# UBTB_MIX_old.net
KiCad netlist of a schematic drawn in EAGLE
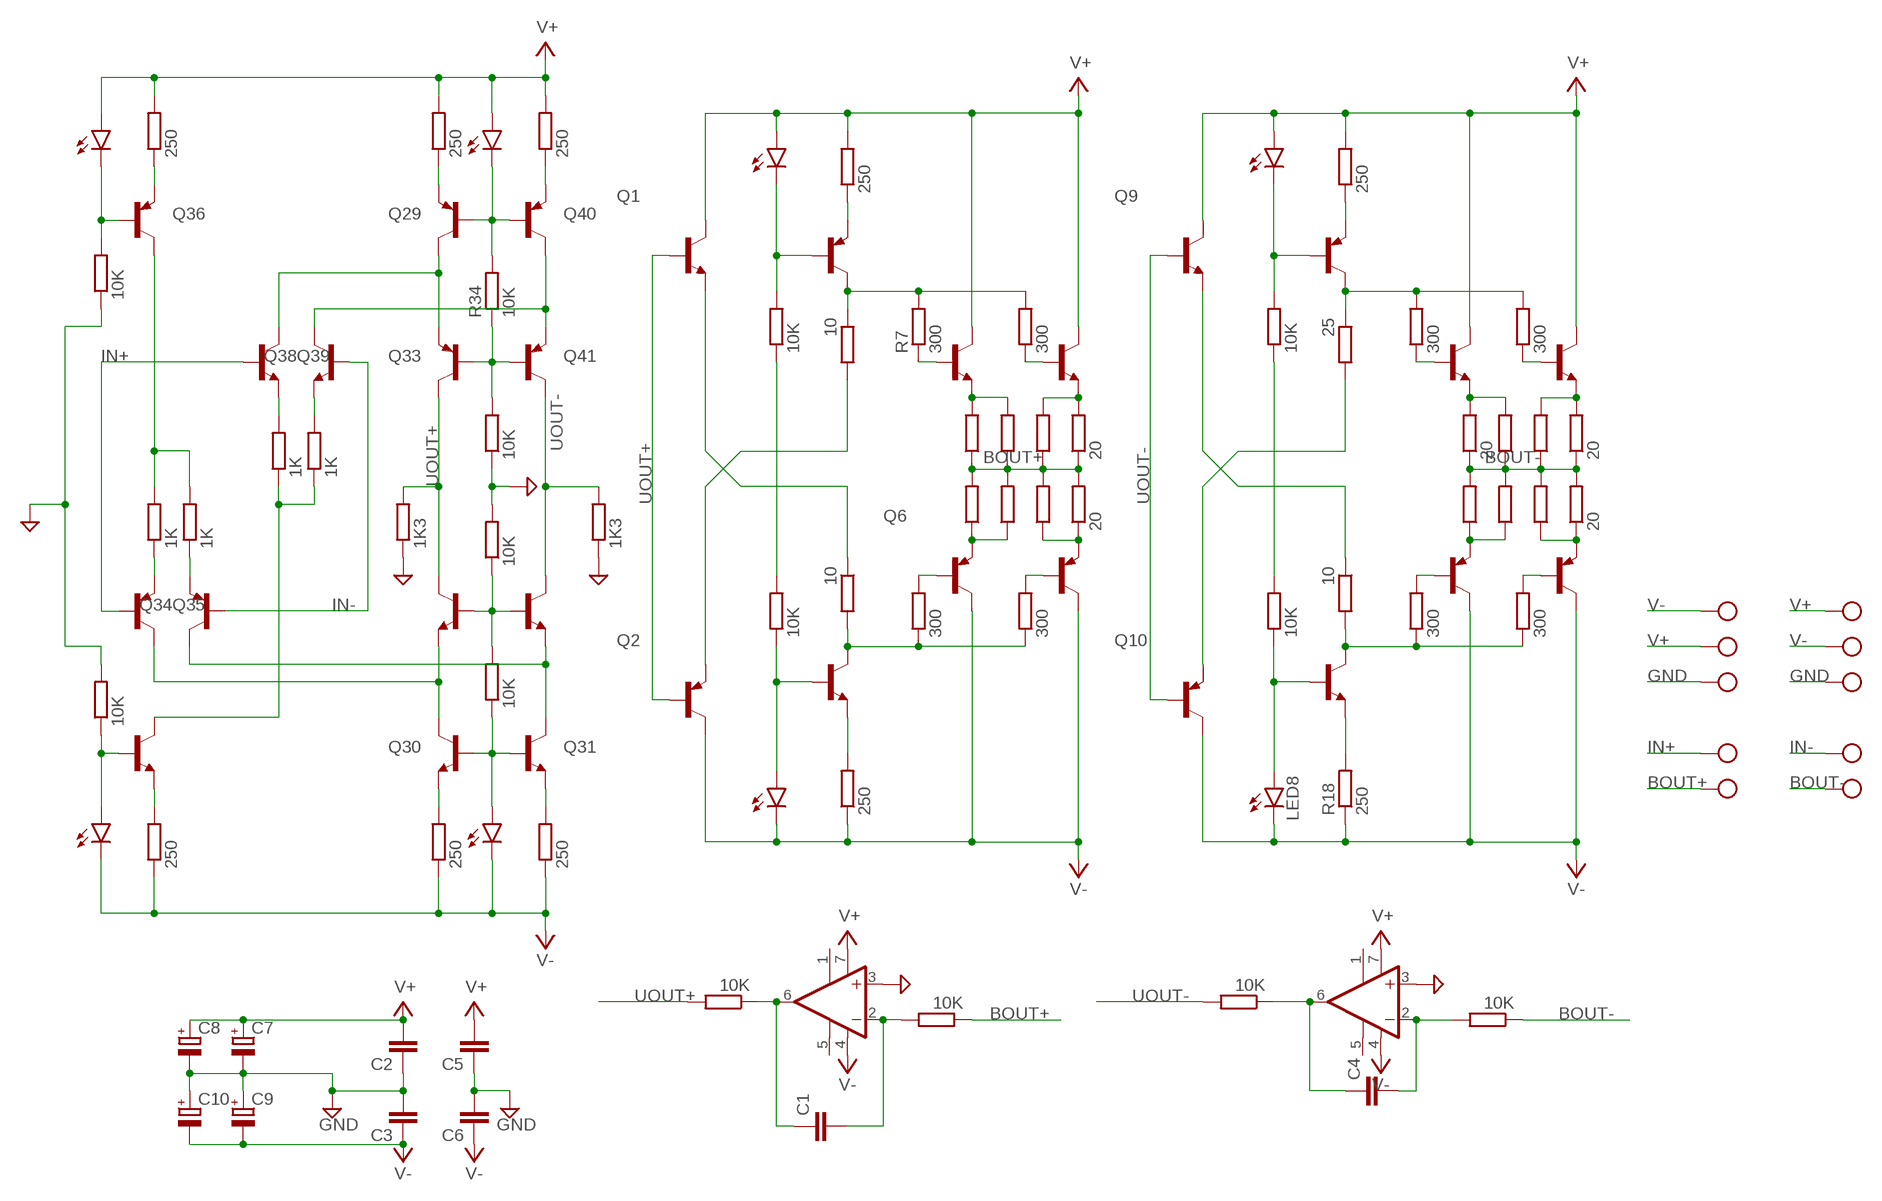
[diagram p0: schematic, sheet 1]

(export (version "E")
  (design (tool "Eeschema 10.0.6"))
  (components
    (comp (ref "C1")
      (value "C-EUC1206")
      (footprint "eagle-import:C1206")
      (libsource (lib "eagle-import") (part "C-EUC1206"))
    )
    (comp (ref "C2")
      (value "C-EUC0805")
      (footprint "eagle-import:C0805")
      (libsource (lib "eagle-import") (part "C-EUC0805"))
    )
    (comp (ref "C3")
      (value "C-EUC0805")
      (footprint "eagle-import:C0805")
      (libsource (lib "eagle-import") (part "C-EUC0805"))
    )
    (comp (ref "C4")
      (value "C-EUC1206")
      (footprint "eagle-import:C1206")
      (libsource (lib "eagle-import") (part "C-EUC1206"))
    )
    (comp (ref "C5")
      (value "C-EUC0805")
      (footprint "eagle-import:C0805")
      (libsource (lib "eagle-import") (part "C-EUC0805"))
    )
    (comp (ref "C6")
      (value "C-EUC0805")
      (footprint "eagle-import:C0805")
      (libsource (lib "eagle-import") (part "C-EUC0805"))
    )
    (comp (ref "C7")
      (value "CPOL-EUF")
      (footprint "eagle-import:PANASONIC_F")
      (libsource (lib "eagle-import") (part "CPOL-EUF"))
    )
    (comp (ref "C8")
      (value "CPOL-EUF")
      (footprint "eagle-import:PANASONIC_F")
      (libsource (lib "eagle-import") (part "CPOL-EUF"))
    )
    (comp (ref "C9")
      (value "CPOL-EUF")
      (footprint "eagle-import:PANASONIC_F")
      (libsource (lib "eagle-import") (part "CPOL-EUF"))
    )
    (comp (ref "C10")
      (value "CPOL-EUF")
      (footprint "eagle-import:PANASONIC_F")
      (libsource (lib "eagle-import") (part "CPOL-EUF"))
    )
    (comp (ref "IC1")
      (value "OPA627U")
      (footprint "eagle-import:SO08")
      (fields (field (name "MF") "TEXAS INSTRUMENTS") (field (name "MPN") "OPA627AU"))
      (libsource (lib "eagle-import") (part "OPA627U"))
    )
    (comp (ref "IC2")
      (value "OPA627U")
      (footprint "eagle-import:SO08")
      (fields (field (name "MF") "TEXAS INSTRUMENTS") (field (name "MPN") "OPA627AU"))
      (libsource (lib "eagle-import") (part "OPA627U"))
    )
    (comp (ref "LED1")
      (value "LEDCHIPLED_1206")
      (footprint "eagle-import:CHIPLED_1206")
      (libsource (lib "eagle-import") (part "LEDCHIPLED_1206"))
    )
    (comp (ref "LED2")
      (value "LEDCHIPLED_1206")
      (footprint "eagle-import:CHIPLED_1206")
      (libsource (lib "eagle-import") (part "LEDCHIPLED_1206"))
    )
    (comp (ref "LED3")
      (value "LEDCHIPLED_1206")
      (footprint "eagle-import:CHIPLED_1206")
      (libsource (lib "eagle-import") (part "LEDCHIPLED_1206"))
    )
    (comp (ref "LED4")
      (value "LEDCHIPLED_1206")
      (footprint "eagle-import:CHIPLED_1206")
      (fields (field (name "SPICEPREFIX") "D"))
      (libsource (lib "eagle-import") (part "LEDCHIPLED_1206"))
    )
    (comp (ref "LED5")
      (value "LEDCHIPLED_1206")
      (footprint "eagle-import:CHIPLED_1206")
      (libsource (lib "eagle-import") (part "LEDCHIPLED_1206"))
    )
    (comp (ref "LED6")
      (value "LEDCHIPLED_1206")
      (footprint "eagle-import:CHIPLED_1206")
      (libsource (lib "eagle-import") (part "LEDCHIPLED_1206"))
    )
    (comp (ref "LED7")
      (value "LEDCHIPLED_1206")
      (footprint "eagle-import:CHIPLED_1206")
      (libsource (lib "eagle-import") (part "LEDCHIPLED_1206"))
    )
    (comp (ref "LED8")
      (value "LEDCHIPLED_1206")
      (footprint "eagle-import:CHIPLED_1206")
      (libsource (lib "eagle-import") (part "LEDCHIPLED_1206"))
    )
    (comp (ref "Q1")
      (value "TRANSISTOR_BC846-NPN-SOT23-BEC")
      (footprint "eagle-import:TRANSISTOR_SOT23-BEC")
      (libsource (lib "eagle-import") (part "TRANSISTOR_-NPN-SOT23-BECBC846"))
    )
    (comp (ref "Q2")
      (value "TRANSISTOR_BC856B-PNP-SOT23-BEC")
      (footprint "eagle-import:TRANSISTOR_SOT23-BEC")
      (libsource (lib "eagle-import") (part "TRANSISTOR_-PNP-SOT23-BECBC856B"))
    )
    (comp (ref "Q3")
      (value "TRANSISTOR_BC846-NPN-SOT23-BEC")
      (footprint "eagle-import:TRANSISTOR_SOT23-BEC")
      (libsource (lib "eagle-import") (part "TRANSISTOR_-NPN-SOT23-BECBC846"))
    )
    (comp (ref "Q4")
      (value "TRANSISTOR_BC856B-PNP-SOT23-BEC")
      (footprint "eagle-import:TRANSISTOR_SOT23-BEC")
      (libsource (lib "eagle-import") (part "TRANSISTOR_-PNP-SOT23-BECBC856B"))
    )
    (comp (ref "Q5")
      (value "TRANSISTOR_BC846-NPN-SOT23-BEC")
      (footprint "eagle-import:TRANSISTOR_SOT23-BEC")
      (libsource (lib "eagle-import") (part "TRANSISTOR_-NPN-SOT23-BECBC846"))
    )
    (comp (ref "Q6")
      (value "TRANSISTOR_BC856B-PNP-SOT23-BEC")
      (footprint "eagle-import:TRANSISTOR_SOT23-BEC")
      (libsource (lib "eagle-import") (part "TRANSISTOR_-PNP-SOT23-BECBC856B"))
    )
    (comp (ref "Q7")
      (value "TRANSISTOR_BC856B-PNP-SOT23-BEC")
      (footprint "eagle-import:TRANSISTOR_SOT23-BEC")
      (libsource (lib "eagle-import") (part "TRANSISTOR_-PNP-SOT23-BECBC856B"))
    )
    (comp (ref "Q8")
      (value "TRANSISTOR_BC846-NPN-SOT23-BEC")
      (footprint "eagle-import:TRANSISTOR_SOT23-BEC")
      (libsource (lib "eagle-import") (part "TRANSISTOR_-NPN-SOT23-BECBC846"))
    )
    (comp (ref "Q9")
      (value "TRANSISTOR_BC846-NPN-SOT23-BEC")
      (footprint "eagle-import:TRANSISTOR_SOT23-BEC")
      (libsource (lib "eagle-import") (part "TRANSISTOR_-NPN-SOT23-BECBC846"))
    )
    (comp (ref "Q10")
      (value "TRANSISTOR_BC856B-PNP-SOT23-BEC")
      (footprint "eagle-import:TRANSISTOR_SOT23-BEC")
      (libsource (lib "eagle-import") (part "TRANSISTOR_-PNP-SOT23-BECBC856B"))
    )
    (comp (ref "Q11")
      (value "TRANSISTOR_BC846-NPN-SOT23-BEC")
      (footprint "eagle-import:TRANSISTOR_SOT23-BEC")
      (libsource (lib "eagle-import") (part "TRANSISTOR_-NPN-SOT23-BECBC846"))
    )
    (comp (ref "Q12")
      (value "TRANSISTOR_BC856B-PNP-SOT23-BEC")
      (footprint "eagle-import:TRANSISTOR_SOT23-BEC")
      (libsource (lib "eagle-import") (part "TRANSISTOR_-PNP-SOT23-BECBC856B"))
    )
    (comp (ref "Q13")
      (value "TRANSISTOR_BC846-NPN-SOT23-BEC")
      (footprint "eagle-import:TRANSISTOR_SOT23-BEC")
      (libsource (lib "eagle-import") (part "TRANSISTOR_-NPN-SOT23-BECBC846"))
    )
    (comp (ref "Q14")
      (value "TRANSISTOR_BC846-NPN-SOT23-BEC")
      (footprint "eagle-import:TRANSISTOR_SOT23-BEC")
      (libsource (lib "eagle-import") (part "TRANSISTOR_-NPN-SOT23-BECBC846"))
    )
    (comp (ref "Q15")
      (value "TRANSISTOR_BC856B-PNP-SOT23-BEC")
      (footprint "eagle-import:TRANSISTOR_SOT23-BEC")
      (libsource (lib "eagle-import") (part "TRANSISTOR_-PNP-SOT23-BECBC856B"))
    )
    (comp (ref "Q16")
      (value "TRANSISTOR_BC856B-PNP-SOT23-BEC")
      (footprint "eagle-import:TRANSISTOR_SOT23-BEC")
      (libsource (lib "eagle-import") (part "TRANSISTOR_-PNP-SOT23-BECBC856B"))
    )
    (comp (ref "Q26")
      (value "BC847CSMD")
      (footprint "eagle-import:SOT23")
      (fields (field (name "SPICEPREFIX") "Q"))
      (libsource (lib "eagle-import") (part "BC847SMDC"))
    )
    (comp (ref "Q29")
      (value "BC857CSMD")
      (footprint "eagle-import:SOT23-BEC")
      (fields (field (name "SPICEPREFIX") "Q"))
      (libsource (lib "eagle-import") (part "BC857SMDC"))
    )
    (comp (ref "Q30")
      (value "BC847CSMD")
      (footprint "eagle-import:SOT23")
      (fields (field (name "SPICEPREFIX") "Q"))
      (libsource (lib "eagle-import") (part "BC847SMDC"))
    )
    (comp (ref "Q31")
      (value "BC847CSMD")
      (footprint "eagle-import:SOT23")
      (fields (field (name "SPICEPREFIX") "Q"))
      (libsource (lib "eagle-import") (part "BC847SMDC"))
    )
    (comp (ref "Q32")
      (value "BC847CSMD")
      (footprint "eagle-import:SOT23")
      (fields (field (name "SPICEPREFIX") "Q"))
      (libsource (lib "eagle-import") (part "BC847SMDC"))
    )
    (comp (ref "Q33")
      (value "BC857CSMD")
      (footprint "eagle-import:SOT23-BEC")
      (fields (field (name "SPICEPREFIX") "Q"))
      (libsource (lib "eagle-import") (part "BC857SMDC"))
    )
    (comp (ref "Q34")
      (value "BC857CSMD")
      (footprint "eagle-import:SOT23-BEC")
      (fields (field (name "SPICEPREFIX") "Q"))
      (libsource (lib "eagle-import") (part "BC857SMDC"))
    )
    (comp (ref "Q35")
      (value "BC857CSMD")
      (footprint "eagle-import:SOT23-BEC")
      (fields (field (name "SPICEPREFIX") "Q"))
      (libsource (lib "eagle-import") (part "BC857SMDC"))
    )
    (comp (ref "Q36")
      (value "BC857CSMD")
      (footprint "eagle-import:SOT23-BEC")
      (fields (field (name "SPICEPREFIX") "Q"))
      (libsource (lib "eagle-import") (part "BC857SMDC"))
    )
    (comp (ref "Q37")
      (value "BC847CSMD")
      (footprint "eagle-import:SOT23")
      (fields (field (name "SPICEPREFIX") "Q"))
      (libsource (lib "eagle-import") (part "BC847SMDC"))
    )
    (comp (ref "Q38")
      (value "BC847CSMD")
      (footprint "eagle-import:SOT23")
      (fields (field (name "SPICEPREFIX") "Q"))
      (libsource (lib "eagle-import") (part "BC847SMDC"))
    )
    (comp (ref "Q39")
      (value "BC847CSMD")
      (footprint "eagle-import:SOT23")
      (fields (field (name "SPICEPREFIX") "Q"))
      (libsource (lib "eagle-import") (part "BC847SMDC"))
    )
    (comp (ref "Q40")
      (value "BC857CSMD")
      (footprint "eagle-import:SOT23-BEC")
      (fields (field (name "SPICEPREFIX") "Q"))
      (libsource (lib "eagle-import") (part "BC857SMDC"))
    )
    (comp (ref "Q41")
      (value "BC857CSMD")
      (footprint "eagle-import:SOT23-BEC")
      (fields (field (name "SPICEPREFIX") "Q"))
      (libsource (lib "eagle-import") (part "BC857SMDC"))
    )
    (comp (ref "R1")
      (value "250")
      (footprint "eagle-import:MINI_MELF-0204W")
      (libsource (lib "eagle-import") (part "R-EU_MELF0204W"))
    )
    (comp (ref "R2")
      (value "250")
      (footprint "eagle-import:MINI_MELF-0204W")
      (libsource (lib "eagle-import") (part "R-EU_MELF0204W"))
    )
    (comp (ref "R3")
      (value "10K")
      (footprint "eagle-import:MINI_MELF-0204W")
      (libsource (lib "eagle-import") (part "R-EU_MELF0204W"))
    )
    (comp (ref "R4")
      (value "10K")
      (footprint "eagle-import:MINI_MELF-0204W")
      (libsource (lib "eagle-import") (part "R-EU_MELF0204W"))
    )
    (comp (ref "R5")
      (value "10")
      (footprint "eagle-import:MINI_MELF-0204W")
      (libsource (lib "eagle-import") (part "R-EU_MELF0204W"))
    )
    (comp (ref "R6")
      (value "10")
      (footprint "eagle-import:MINI_MELF-0204W")
      (libsource (lib "eagle-import") (part "R-EU_MELF0204W"))
    )
    (comp (ref "R7")
      (value "300")
      (footprint "eagle-import:MINI_MELF-0204W")
      (libsource (lib "eagle-import") (part "R-EU_MELF0204W"))
    )
    (comp (ref "R8")
      (value "300")
      (footprint "eagle-import:MINI_MELF-0204W")
      (libsource (lib "eagle-import") (part "R-EU_MELF0204W"))
    )
    (comp (ref "R9")
      (value "300")
      (footprint "eagle-import:MINI_MELF-0204W")
      (libsource (lib "eagle-import") (part "R-EU_MELF0204W"))
    )
    (comp (ref "R10")
      (value "300")
      (footprint "eagle-import:MINI_MELF-0204W")
      (libsource (lib "eagle-import") (part "R-EU_MELF0204W"))
    )
    (comp (ref "R11")
      (value "R-EU_MELF0204W")
      (footprint "eagle-import:MINI_MELF-0204W")
      (libsource (lib "eagle-import") (part "R-EU_MELF0204W"))
    )
    (comp (ref "R12")
      (value "R-EU_MELF0204W")
      (footprint "eagle-import:MINI_MELF-0204W")
      (libsource (lib "eagle-import") (part "R-EU_MELF0204W"))
    )
    (comp (ref "R13")
      (value "20")
      (footprint "eagle-import:MINI_MELF-0204W")
      (libsource (lib "eagle-import") (part "R-EU_MELF0204W"))
    )
    (comp (ref "R14")
      (value "20")
      (footprint "eagle-import:MINI_MELF-0204W")
      (libsource (lib "eagle-import") (part "R-EU_MELF0204W"))
    )
    (comp (ref "R15")
      (value "250")
      (footprint "eagle-import:MINI_MELF-0204W")
      (libsource (lib "eagle-import") (part "R-EU_MELF0204W"))
    )
    (comp (ref "R16")
      (value "10K")
      (footprint "eagle-import:MINI_MELF-0204W")
      (libsource (lib "eagle-import") (part "R-EU_MELF0204W"))
    )
    (comp (ref "R17")
      (value "10K")
      (footprint "eagle-import:MINI_MELF-0204W")
      (libsource (lib "eagle-import") (part "R-EU_MELF0204W"))
    )
    (comp (ref "R18")
      (value "250")
      (footprint "eagle-import:MINI_MELF-0204W")
      (libsource (lib "eagle-import") (part "R-EU_MELF0204W"))
    )
    (comp (ref "R19")
      (value "10K")
      (footprint "eagle-import:MINI_MELF-0204W")
      (libsource (lib "eagle-import") (part "R-EU_MELF0204W"))
    )
    (comp (ref "R20")
      (value "10K")
      (footprint "eagle-import:MINI_MELF-0204W")
      (libsource (lib "eagle-import") (part "R-EU_MELF0204W"))
    )
    (comp (ref "R21")
      (value "25")
      (footprint "eagle-import:MINI_MELF-0204W")
      (libsource (lib "eagle-import") (part "R-EU_MELF0204W"))
    )
    (comp (ref "R22")
      (value "250")
      (footprint "eagle-import:MINI_MELF-0204W")
      (libsource (lib "eagle-import") (part "R-EU_MELF0204W"))
    )
    (comp (ref "R23")
      (value "250")
      (footprint "eagle-import:MINI_MELF-0204W")
      (libsource (lib "eagle-import") (part "R-EU_MELF0204W"))
    )
    (comp (ref "R24")
      (value "10")
      (footprint "eagle-import:MINI_MELF-0204W")
      (libsource (lib "eagle-import") (part "R-EU_MELF0204W"))
    )
    (comp (ref "R25")
      (value "300")
      (footprint "eagle-import:MINI_MELF-0204W")
      (libsource (lib "eagle-import") (part "R-EU_MELF0204W"))
    )
    (comp (ref "R26")
      (value "300")
      (footprint "eagle-import:MINI_MELF-0204W")
      (libsource (lib "eagle-import") (part "R-EU_MELF0204W"))
    )
    (comp (ref "R27")
      (value "300")
      (footprint "eagle-import:MINI_MELF-0204W")
      (libsource (lib "eagle-import") (part "R-EU_MELF0204W"))
    )
    (comp (ref "R28")
      (value "300")
      (footprint "eagle-import:MINI_MELF-0204W")
      (libsource (lib "eagle-import") (part "R-EU_MELF0204W"))
    )
    (comp (ref "R29")
      (value "10K")
      (footprint "eagle-import:MINI_MELF-0204W")
      (libsource (lib "eagle-import") (part "R-EU_MELF0204W"))
    )
    (comp (ref "R30")
      (value "20")
      (footprint "eagle-import:MINI_MELF-0204W")
      (libsource (lib "eagle-import") (part "R-EU_MELF0204W"))
    )
    (comp (ref "R31")
      (value "R-EU_MELF0204W")
      (footprint "eagle-import:MINI_MELF-0204W")
      (libsource (lib "eagle-import") (part "R-EU_MELF0204W"))
    )
    (comp (ref "R32")
      (value "10K")
      (footprint "eagle-import:MINI_MELF-0204W")
      (libsource (lib "eagle-import") (part "R-EU_MELF0204W"))
    )
    (comp (ref "R33")
      (value "10K")
      (footprint "eagle-import:MINI_MELF-0204W")
      (libsource (lib "eagle-import") (part "R-EU_MELF0204W"))
    )
    (comp (ref "R34")
      (value "10K")
      (footprint "eagle-import:MINI_MELF-0204W")
      (libsource (lib "eagle-import") (part "R-EU_MELF0204W"))
    )
    (comp (ref "R35")
      (value "250")
      (footprint "eagle-import:MINI_MELF-0204W")
      (libsource (lib "eagle-import") (part "R-EU_MELF0204W"))
    )
    (comp (ref "R36")
      (value "250")
      (footprint "eagle-import:MINI_MELF-0204W")
      (libsource (lib "eagle-import") (part "R-EU_MELF0204W"))
    )
    (comp (ref "R37")
      (value "1K3")
      (footprint "eagle-import:MINI_MELF-0204W")
      (libsource (lib "eagle-import") (part "R-EU_MELF0204W"))
    )
    (comp (ref "R38")
      (value "1K3")
      (footprint "eagle-import:MINI_MELF-0204W")
      (libsource (lib "eagle-import") (part "R-EU_MELF0204W"))
    )
    (comp (ref "R39")
      (value "1K")
      (footprint "eagle-import:MINI_MELF-0204W")
      (libsource (lib "eagle-import") (part "R-EU_MELF0204W"))
    )
    (comp (ref "R40")
      (value "1K")
      (footprint "eagle-import:MINI_MELF-0204W")
      (libsource (lib "eagle-import") (part "R-EU_MELF0204W"))
    )
    (comp (ref "R41")
      (value "1K")
      (footprint "eagle-import:MINI_MELF-0204W")
      (libsource (lib "eagle-import") (part "R-EU_MELF0204W"))
    )
    (comp (ref "R42")
      (value "1K")
      (footprint "eagle-import:MINI_MELF-0204W")
      (libsource (lib "eagle-import") (part "R-EU_MELF0204W"))
    )
    (comp (ref "R43")
      (value "250")
      (footprint "eagle-import:MINI_MELF-0204W")
      (libsource (lib "eagle-import") (part "R-EU_MELF0204W"))
    )
    (comp (ref "R44")
      (value "250")
      (footprint "eagle-import:MINI_MELF-0204W")
      (fields (field (name "SPICEPREFIX") "R"))
      (libsource (lib "eagle-import") (part "R-EU_MELF0204W"))
    )
    (comp (ref "R45")
      (value "10K")
      (footprint "eagle-import:MINI_MELF-0204W")
      (libsource (lib "eagle-import") (part "R-EU_MELF0204W"))
    )
    (comp (ref "R46")
      (value "10K")
      (footprint "eagle-import:MINI_MELF-0204W")
      (libsource (lib "eagle-import") (part "R-EU_MELF0204W"))
    )
    (comp (ref "R47")
      (value "20")
      (footprint "eagle-import:MINI_MELF-0204W")
      (libsource (lib "eagle-import") (part "R-EU_MELF0204W"))
    )
    (comp (ref "R48")
      (value "10K")
      (footprint "eagle-import:MINI_MELF-0204W")
      (libsource (lib "eagle-import") (part "R-EU_MELF0204W"))
    )
    (comp (ref "R49")
      (value "20")
      (footprint "eagle-import:MINI_MELF-0204W")
      (libsource (lib "eagle-import") (part "R-EU_MELF0204W"))
    )
    (comp (ref "R50")
      (value "R-EU_MELF0204W")
      (footprint "eagle-import:MINI_MELF-0204W")
      (libsource (lib "eagle-import") (part "R-EU_MELF0204W"))
    )
    (comp (ref "R51")
      (value "10K")
      (footprint "eagle-import:MINI_MELF-0204W")
      (libsource (lib "eagle-import") (part "R-EU_MELF0204W"))
    )
    (comp (ref "R52")
      (value "R-EU_MELF0204W")
      (footprint "eagle-import:MINI_MELF-0204W")
      (libsource (lib "eagle-import") (part "R-EU_MELF0204W"))
    )
    (comp (ref "R53")
      (value "R-EU_MELF0204W")
      (footprint "eagle-import:MINI_MELF-0204W")
      (libsource (lib "eagle-import") (part "R-EU_MELF0204W"))
    )
    (comp (ref "R54")
      (value "R-EU_MELF0204W")
      (footprint "eagle-import:MINI_MELF-0204W")
      (libsource (lib "eagle-import") (part "R-EU_MELF0204W"))
    )
    (comp (ref "R55")
      (value "R-EU_MELF0204W")
      (footprint "eagle-import:MINI_MELF-0204W")
      (libsource (lib "eagle-import") (part "R-EU_MELF0204W"))
    )
    (comp (ref "R56")
      (value "R-EU_MELF0204W")
      (footprint "eagle-import:MINI_MELF-0204W")
      (libsource (lib "eagle-import") (part "R-EU_MELF0204W"))
    )
    (comp (ref "R57")
      (value "R-EU_MELF0204W")
      (footprint "eagle-import:MINI_MELF-0204W")
      (libsource (lib "eagle-import") (part "R-EU_MELF0204W"))
    )
    (comp (ref "R58")
      (value "R-EU_MELF0204W")
      (footprint "eagle-import:MINI_MELF-0204W")
      (libsource (lib "eagle-import") (part "R-EU_MELF0204W"))
    )
    (comp (ref "X1")
      (value "CON-PHOENIX-508_MKDSN1,5/3-5,08")
      (footprint "eagle-import:CON-PHOENIX-508_MKDSN1,5_3-5,08")
      (libsource (lib "eagle-import") (part "CON-PHOENIX-508_MKDSN1,5/3-5,08"))
    )
    (comp (ref "X2")
      (value "CON-PHOENIX-508_MKDSN1,5/3-5,08")
      (footprint "eagle-import:CON-PHOENIX-508_MKDSN1,5_3-5,08")
      (libsource (lib "eagle-import") (part "CON-PHOENIX-508_MKDSN1,5/3-5,08"))
    )
    (comp (ref "X3")
      (value "CON-PHOENIX-508_MKDSN1,5/2-5,08")
      (footprint "eagle-import:CON-PHOENIX-508_MKDSN1,5_2-5,08")
      (libsource (lib "eagle-import") (part "CON-PHOENIX-508_MKDSN1,5/2-5,08"))
    )
    (comp (ref "X4")
      (value "CON-PHOENIX-508_MKDSN1,5/2-5,08")
      (footprint "eagle-import:CON-PHOENIX-508_MKDSN1,5_2-5,08")
      (libsource (lib "eagle-import") (part "CON-PHOENIX-508_MKDSN1,5/2-5,08"))
    )
  )
  (nets
    (net (code "1") (name "/BOUT+") (class "Default")
      (node (ref "R11") (pin "1") (pinfunction "1_1") (pintype "passive"))
      (node (ref "R12") (pin "2") (pinfunction "2_2") (pintype "passive"))
      (node (ref "R13") (pin "1") (pinfunction "1_1") (pintype "passive"))
      (node (ref "R14") (pin "2") (pinfunction "2_2") (pintype "passive"))
      (node (ref "R17") (pin "1") (pinfunction "1_1") (pintype "passive"))
      (node (ref "R50") (pin "1") (pinfunction "1_1") (pintype "passive"))
      (node (ref "R52") (pin "1") (pinfunction "1_1") (pintype "passive"))
      (node (ref "R53") (pin "2") (pinfunction "2_2") (pintype "passive"))
      (node (ref "R54") (pin "2") (pinfunction "2_2") (pintype "passive"))
      (node (ref "X3") (pin "2") (pinfunction "KL_2") (pintype "passive"))
    )
    (net (code "2") (name "/BOUT-") (class "Default")
      (node (ref "R30") (pin "1") (pinfunction "1_1") (pintype "passive"))
      (node (ref "R31") (pin "2") (pinfunction "2_2") (pintype "passive"))
      (node (ref "R47") (pin "1") (pinfunction "1_1") (pintype "passive"))
      (node (ref "R48") (pin "1") (pinfunction "1_1") (pintype "passive"))
      (node (ref "R49") (pin "2") (pinfunction "2_2") (pintype "passive"))
      (node (ref "R55") (pin "1") (pinfunction "1_1") (pintype "passive"))
      (node (ref "R56") (pin "1") (pinfunction "1_1") (pintype "passive"))
      (node (ref "R57") (pin "2") (pinfunction "2_2") (pintype "passive"))
      (node (ref "R58") (pin "2") (pinfunction "2_2") (pintype "passive"))
      (node (ref "X4") (pin "2") (pinfunction "KL_2") (pintype "passive"))
    )
    (net (code "3") (name "/IN+") (class "Default")
      (node (ref "Q35") (pin "B") (pinfunction "B_B") (pintype "passive"))
      (node (ref "Q39") (pin "1") (pinfunction "B_1") (pintype "passive"))
      (node (ref "X3") (pin "1") (pinfunction "KL_1") (pintype "passive"))
    )
    (net (code "4") (name "/IN-") (class "Default")
      (node (ref "Q34") (pin "B") (pinfunction "B_B") (pintype "passive"))
      (node (ref "Q38") (pin "1") (pinfunction "B_1") (pintype "passive"))
      (node (ref "X4") (pin "1") (pinfunction "KL_1") (pintype "passive"))
    )
    (net (code "5") (name "/UOUT+") (class "Default")
      (node (ref "Q1") (pin "B") (pinfunction "B_B") (pintype "passive"))
      (node (ref "Q2") (pin "B") (pinfunction "B_B") (pintype "passive"))
      (node (ref "Q33") (pin "C") (pinfunction "C_C") (pintype "passive"))
      (node (ref "Q37") (pin "3") (pinfunction "C_3") (pintype "passive"))
      (node (ref "R16") (pin "2") (pinfunction "2_2") (pintype "passive"))
      (node (ref "R37") (pin "2") (pinfunction "2_2") (pintype "passive"))
    )
    (net (code "6") (name "/UOUT-") (class "Default")
      (node (ref "Q10") (pin "B") (pinfunction "B_B") (pintype "passive"))
      (node (ref "Q32") (pin "3") (pinfunction "C_3") (pintype "passive"))
      (node (ref "Q41") (pin "C") (pinfunction "C_C") (pintype "passive"))
      (node (ref "Q9") (pin "B") (pinfunction "B_B") (pintype "passive"))
      (node (ref "R38") (pin "2") (pinfunction "2_2") (pintype "passive"))
      (node (ref "R51") (pin "2") (pinfunction "2_2") (pintype "passive"))
    )
    (net (code "7") (name "GND") (class "Default")
      (node (ref "C10") (pin "+") (pinfunction "+_+") (pintype "passive"))
      (node (ref "C2") (pin "1") (pinfunction "1_1") (pintype "passive"))
      (node (ref "C3") (pin "2") (pinfunction "2_2") (pintype "passive"))
      (node (ref "C5") (pin "1") (pinfunction "1_1") (pintype "passive"))
      (node (ref "C6") (pin "2") (pinfunction "2_2") (pintype "passive"))
      (node (ref "C7") (pin "-") (pinfunction "-_-") (pintype "passive"))
      (node (ref "C8") (pin "-") (pinfunction "-_-") (pintype "passive"))
      (node (ref "C9") (pin "+") (pinfunction "+_+") (pintype "passive"))
      (node (ref "IC1") (pin "3") (pinfunction "+IN_3") (pintype "input"))
      (node (ref "IC2") (pin "3") (pinfunction "+IN_3") (pintype "input"))
      (node (ref "R32") (pin "2") (pinfunction "2_2") (pintype "passive"))
      (node (ref "R33") (pin "1") (pinfunction "1_1") (pintype "passive"))
      (node (ref "R37") (pin "1") (pinfunction "1_1") (pintype "passive"))
      (node (ref "R38") (pin "1") (pinfunction "1_1") (pintype "passive"))
      (node (ref "R45") (pin "1") (pinfunction "1_1") (pintype "passive"))
      (node (ref "R46") (pin "2") (pinfunction "2_2") (pintype "passive"))
      (node (ref "X1") (pin "3") (pinfunction "KL_3") (pintype "passive"))
      (node (ref "X2") (pin "3") (pinfunction "KL_3") (pintype "passive"))
    )
    (net (code "8") (name "Net-(IC1--IN)") (class "Default")
      (node (ref "C1") (pin "2") (pinfunction "2_2") (pintype "passive"))
      (node (ref "IC1") (pin "2") (pinfunction "-IN_2") (pintype "input"))
      (node (ref "R17") (pin "2") (pinfunction "2_2") (pintype "passive"))
    )
    (net (code "9") (name "Net-(IC1-OUT)") (class "Default")
      (node (ref "C1") (pin "1") (pinfunction "1_1") (pintype "passive"))
      (node (ref "IC1") (pin "6") (pinfunction "OUT_6") (pintype "output"))
      (node (ref "R16") (pin "1") (pinfunction "1_1") (pintype "passive"))
    )
    (net (code "10") (name "Net-(IC2--IN)") (class "Default")
      (node (ref "C4") (pin "2") (pinfunction "2_2") (pintype "passive"))
      (node (ref "IC2") (pin "2") (pinfunction "-IN_2") (pintype "input"))
      (node (ref "R48") (pin "2") (pinfunction "2_2") (pintype "passive"))
    )
    (net (code "11") (name "Net-(IC2-OUT)") (class "Default")
      (node (ref "C4") (pin "1") (pinfunction "1_1") (pintype "passive"))
      (node (ref "IC2") (pin "6") (pinfunction "OUT_6") (pintype "output"))
      (node (ref "R51") (pin "1") (pinfunction "1_1") (pintype "passive"))
    )
    (net (code "12") (name "Net-(LED2-PadC)") (class "Default")
      (node (ref "LED2") (pin "C") (pinfunction "C_C") (pintype "passive"))
      (node (ref "Q29") (pin "B") (pinfunction "B_B") (pintype "passive"))
      (node (ref "Q40") (pin "B") (pinfunction "B_B") (pintype "passive"))
      (node (ref "R34") (pin "2") (pinfunction "2_2") (pintype "passive"))
    )
    (net (code "13") (name "Net-(LED3-PadC)") (class "Default")
      (node (ref "LED3") (pin "C") (pinfunction "C_C") (pintype "passive"))
      (node (ref "Q36") (pin "B") (pinfunction "B_B") (pintype "passive"))
      (node (ref "R45") (pin "2") (pinfunction "2_2") (pintype "passive"))
    )
    (net (code "14") (name "Net-(LED5-PadC)") (class "Default")
      (node (ref "LED5") (pin "C") (pinfunction "C_C") (pintype "passive"))
      (node (ref "Q4") (pin "B") (pinfunction "B_B") (pintype "passive"))
      (node (ref "R3") (pin "2") (pinfunction "2_2") (pintype "passive"))
    )
    (net (code "15") (name "Net-(LED6-PadA)") (class "Default")
      (node (ref "LED6") (pin "A") (pinfunction "A_A") (pintype "passive"))
      (node (ref "Q3") (pin "B") (pinfunction "B_B") (pintype "passive"))
      (node (ref "R4") (pin "1") (pinfunction "1_1") (pintype "passive"))
    )
    (net (code "16") (name "Net-(LED7-PadC)") (class "Default")
      (node (ref "LED7") (pin "C") (pinfunction "C_C") (pintype "passive"))
      (node (ref "Q12") (pin "B") (pinfunction "B_B") (pintype "passive"))
      (node (ref "R19") (pin "2") (pinfunction "2_2") (pintype "passive"))
    )
    (net (code "17") (name "Net-(LED8-PadA)") (class "Default")
      (node (ref "LED8") (pin "A") (pinfunction "A_A") (pintype "passive"))
      (node (ref "Q11") (pin "B") (pinfunction "B_B") (pintype "passive"))
      (node (ref "R20") (pin "1") (pinfunction "1_1") (pintype "passive"))
    )
    (net (code "18") (name "Net-(Q1-PadE)") (class "Default")
      (node (ref "Q1") (pin "E") (pinfunction "E_E") (pintype "passive"))
      (node (ref "R6") (pin "1") (pinfunction "1_1") (pintype "passive"))
    )
    (net (code "19") (name "Net-(Q2-PadE)") (class "Default")
      (node (ref "Q2") (pin "E") (pinfunction "E_E") (pintype "passive"))
      (node (ref "R5") (pin "2") (pinfunction "2_2") (pintype "passive"))
    )
    (net (code "20") (name "Net-(Q3-PadC)") (class "Default")
      (node (ref "Q3") (pin "C") (pinfunction "C_C") (pintype "passive"))
      (node (ref "R6") (pin "2") (pinfunction "2_2") (pintype "passive"))
      (node (ref "R8") (pin "1") (pinfunction "1_1") (pintype "passive"))
      (node (ref "R9") (pin "1") (pinfunction "1_1") (pintype "passive"))
    )
    (net (code "21") (name "Net-(Q3-PadE)") (class "Default")
      (node (ref "Q3") (pin "E") (pinfunction "E_E") (pintype "passive"))
      (node (ref "R2") (pin "2") (pinfunction "2_2") (pintype "passive"))
    )
    (net (code "22") (name "Net-(Q4-PadC)") (class "Default")
      (node (ref "Q4") (pin "C") (pinfunction "C_C") (pintype "passive"))
      (node (ref "R10") (pin "2") (pinfunction "2_2") (pintype "passive"))
      (node (ref "R5") (pin "1") (pinfunction "1_1") (pintype "passive"))
      (node (ref "R7") (pin "2") (pinfunction "2_2") (pintype "passive"))
    )
    (net (code "23") (name "Net-(Q4-PadE)") (class "Default")
      (node (ref "Q4") (pin "E") (pinfunction "E_E") (pintype "passive"))
      (node (ref "R1") (pin "1") (pinfunction "1_1") (pintype "passive"))
    )
    (net (code "24") (name "Net-(Q5-PadB)") (class "Default")
      (node (ref "Q5") (pin "B") (pinfunction "B_B") (pintype "passive"))
      (node (ref "R7") (pin "1") (pinfunction "1_1") (pintype "passive"))
    )
    (net (code "25") (name "Net-(Q5-PadE)") (class "Default")
      (node (ref "Q5") (pin "E") (pinfunction "E_E") (pintype "passive"))
      (node (ref "R11") (pin "2") (pinfunction "2_2") (pintype "passive"))
      (node (ref "R50") (pin "2") (pinfunction "2_2") (pintype "passive"))
    )
    (net (code "26") (name "Net-(Q6-PadB)") (class "Default")
      (node (ref "Q6") (pin "B") (pinfunction "B_B") (pintype "passive"))
      (node (ref "R8") (pin "2") (pinfunction "2_2") (pintype "passive"))
    )
    (net (code "27") (name "Net-(Q6-PadE)") (class "Default")
      (node (ref "Q6") (pin "E") (pinfunction "E_E") (pintype "passive"))
      (node (ref "R12") (pin "1") (pinfunction "1_1") (pintype "passive"))
      (node (ref "R53") (pin "1") (pinfunction "1_1") (pintype "passive"))
    )
    (net (code "28") (name "Net-(Q7-PadB)") (class "Default")
      (node (ref "Q7") (pin "B") (pinfunction "B_B") (pintype "passive"))
      (node (ref "R9") (pin "2") (pinfunction "2_2") (pintype "passive"))
    )
    (net (code "29") (name "Net-(Q7-PadE)") (class "Default")
      (node (ref "Q7") (pin "E") (pinfunction "E_E") (pintype "passive"))
      (node (ref "R14") (pin "1") (pinfunction "1_1") (pintype "passive"))
      (node (ref "R54") (pin "1") (pinfunction "1_1") (pintype "passive"))
    )
    (net (code "30") (name "Net-(Q8-PadB)") (class "Default")
      (node (ref "Q8") (pin "B") (pinfunction "B_B") (pintype "passive"))
      (node (ref "R10") (pin "1") (pinfunction "1_1") (pintype "passive"))
    )
    (net (code "31") (name "Net-(Q8-PadE)") (class "Default")
      (node (ref "Q8") (pin "E") (pinfunction "E_E") (pintype "passive"))
      (node (ref "R13") (pin "2") (pinfunction "2_2") (pintype "passive"))
      (node (ref "R52") (pin "2") (pinfunction "2_2") (pintype "passive"))
    )
    (net (code "32") (name "Net-(Q9-PadE)") (class "Default")
      (node (ref "Q9") (pin "E") (pinfunction "E_E") (pintype "passive"))
      (node (ref "R24") (pin "1") (pinfunction "1_1") (pintype "passive"))
    )
    (net (code "33") (name "Net-(Q10-PadE)") (class "Default")
      (node (ref "Q10") (pin "E") (pinfunction "E_E") (pintype "passive"))
      (node (ref "R21") (pin "2") (pinfunction "2_2") (pintype "passive"))
    )
    (net (code "34") (name "Net-(Q11-PadC)") (class "Default")
      (node (ref "Q11") (pin "C") (pinfunction "C_C") (pintype "passive"))
      (node (ref "R24") (pin "2") (pinfunction "2_2") (pintype "passive"))
      (node (ref "R26") (pin "1") (pinfunction "1_1") (pintype "passive"))
      (node (ref "R27") (pin "1") (pinfunction "1_1") (pintype "passive"))
    )
    (net (code "35") (name "Net-(Q11-PadE)") (class "Default")
      (node (ref "Q11") (pin "E") (pinfunction "E_E") (pintype "passive"))
      (node (ref "R18") (pin "2") (pinfunction "2_2") (pintype "passive"))
    )
    (net (code "36") (name "Net-(Q12-PadC)") (class "Default")
      (node (ref "Q12") (pin "C") (pinfunction "C_C") (pintype "passive"))
      (node (ref "R21") (pin "1") (pinfunction "1_1") (pintype "passive"))
      (node (ref "R25") (pin "2") (pinfunction "2_2") (pintype "passive"))
      (node (ref "R28") (pin "2") (pinfunction "2_2") (pintype "passive"))
    )
    (net (code "37") (name "Net-(Q12-PadE)") (class "Default")
      (node (ref "Q12") (pin "E") (pinfunction "E_E") (pintype "passive"))
      (node (ref "R15") (pin "1") (pinfunction "1_1") (pintype "passive"))
    )
    (net (code "38") (name "Net-(Q13-PadB)") (class "Default")
      (node (ref "Q13") (pin "B") (pinfunction "B_B") (pintype "passive"))
      (node (ref "R25") (pin "1") (pinfunction "1_1") (pintype "passive"))
    )
    (net (code "39") (name "Net-(Q13-PadE)") (class "Default")
      (node (ref "Q13") (pin "E") (pinfunction "E_E") (pintype "passive"))
      (node (ref "R30") (pin "2") (pinfunction "2_2") (pintype "passive"))
      (node (ref "R55") (pin "2") (pinfunction "2_2") (pintype "passive"))
    )
    (net (code "40") (name "Net-(Q14-PadB)") (class "Default")
      (node (ref "Q14") (pin "B") (pinfunction "B_B") (pintype "passive"))
      (node (ref "R28") (pin "1") (pinfunction "1_1") (pintype "passive"))
    )
    (net (code "41") (name "Net-(Q14-PadE)") (class "Default")
      (node (ref "Q14") (pin "E") (pinfunction "E_E") (pintype "passive"))
      (node (ref "R47") (pin "2") (pinfunction "2_2") (pintype "passive"))
      (node (ref "R56") (pin "2") (pinfunction "2_2") (pintype "passive"))
    )
    (net (code "42") (name "Net-(Q15-PadB)") (class "Default")
      (node (ref "Q15") (pin "B") (pinfunction "B_B") (pintype "passive"))
      (node (ref "R26") (pin "2") (pinfunction "2_2") (pintype "passive"))
    )
    (net (code "43") (name "Net-(Q15-PadE)") (class "Default")
      (node (ref "Q15") (pin "E") (pinfunction "E_E") (pintype "passive"))
      (node (ref "R31") (pin "1") (pinfunction "1_1") (pintype "passive"))
      (node (ref "R58") (pin "1") (pinfunction "1_1") (pintype "passive"))
    )
    (net (code "44") (name "Net-(Q16-PadB)") (class "Default")
      (node (ref "Q16") (pin "B") (pinfunction "B_B") (pintype "passive"))
      (node (ref "R27") (pin "2") (pinfunction "2_2") (pintype "passive"))
    )
    (net (code "45") (name "Net-(Q16-PadE)") (class "Default")
      (node (ref "Q16") (pin "E") (pinfunction "E_E") (pintype "passive"))
      (node (ref "R49") (pin "1") (pinfunction "1_1") (pintype "passive"))
      (node (ref "R57") (pin "1") (pinfunction "1_1") (pintype "passive"))
    )
    (net (code "46") (name "Net-(Q26-B)") (class "Default")
      (node (ref "LED4") (pin "A") (pinfunction "A_A") (pintype "passive"))
      (node (ref "Q26") (pin "1") (pinfunction "B_1") (pintype "passive"))
      (node (ref "R46") (pin "1") (pinfunction "1_1") (pintype "passive"))
    )
    (net (code "47") (name "Net-(Q26-C)") (class "Default")
      (node (ref "Q26") (pin "3") (pinfunction "C_3") (pintype "passive"))
      (node (ref "R39") (pin "1") (pinfunction "1_1") (pintype "passive"))
      (node (ref "R40") (pin "1") (pinfunction "1_1") (pintype "passive"))
    )
    (net (code "48") (name "Net-(Q26-E)") (class "Default")
      (node (ref "Q26") (pin "2") (pinfunction "E_2") (pintype "passive"))
      (node (ref "R44") (pin "2") (pinfunction "2_2") (pintype "passive"))
    )
    (net (code "49") (name "Net-(Q29-PadE)") (class "Default")
      (node (ref "Q29") (pin "E") (pinfunction "E_E") (pintype "passive"))
      (node (ref "R35") (pin "1") (pinfunction "1_1") (pintype "passive"))
    )
    (net (code "50") (name "Net-(Q30-B)") (class "Default")
      (node (ref "LED1") (pin "A") (pinfunction "A_A") (pintype "passive"))
      (node (ref "Q30") (pin "1") (pinfunction "B_1") (pintype "passive"))
      (node (ref "Q31") (pin "1") (pinfunction "B_1") (pintype "passive"))
      (node (ref "R29") (pin "1") (pinfunction "1_1") (pintype "passive"))
    )
    (net (code "51") (name "Net-(Q30-C)") (class "Default")
      (node (ref "Q30") (pin "3") (pinfunction "C_3") (pintype "passive"))
      (node (ref "Q35") (pin "C") (pinfunction "C_C") (pintype "passive"))
      (node (ref "Q37") (pin "2") (pinfunction "E_2") (pintype "passive"))
    )
    (net (code "52") (name "Net-(Q30-E)") (class "Default")
      (node (ref "Q30") (pin "2") (pinfunction "E_2") (pintype "passive"))
      (node (ref "R22") (pin "2") (pinfunction "2_2") (pintype "passive"))
    )
    (net (code "53") (name "Net-(Q31-C)") (class "Default")
      (node (ref "Q31") (pin "3") (pinfunction "C_3") (pintype "passive"))
      (node (ref "Q32") (pin "2") (pinfunction "E_2") (pintype "passive"))
      (node (ref "Q34") (pin "C") (pinfunction "C_C") (pintype "passive"))
    )
    (net (code "54") (name "Net-(Q31-E)") (class "Default")
      (node (ref "Q31") (pin "2") (pinfunction "E_2") (pintype "passive"))
      (node (ref "R23") (pin "2") (pinfunction "2_2") (pintype "passive"))
    )
    (net (code "55") (name "Net-(Q32-B)") (class "Default")
      (node (ref "Q32") (pin "1") (pinfunction "B_1") (pintype "passive"))
      (node (ref "Q37") (pin "1") (pinfunction "B_1") (pintype "passive"))
      (node (ref "R29") (pin "2") (pinfunction "2_2") (pintype "passive"))
      (node (ref "R32") (pin "1") (pinfunction "1_1") (pintype "passive"))
    )
    (net (code "56") (name "Net-(Q33-PadB)") (class "Default")
      (node (ref "Q33") (pin "B") (pinfunction "B_B") (pintype "passive"))
      (node (ref "Q41") (pin "B") (pinfunction "B_B") (pintype "passive"))
      (node (ref "R33") (pin "2") (pinfunction "2_2") (pintype "passive"))
      (node (ref "R34") (pin "1") (pinfunction "1_1") (pintype "passive"))
    )
    (net (code "57") (name "Net-(Q34-PadE)") (class "Default")
      (node (ref "Q34") (pin "E") (pinfunction "E_E") (pintype "passive"))
      (node (ref "R42") (pin "1") (pinfunction "1_1") (pintype "passive"))
    )
    (net (code "58") (name "Net-(Q35-PadE)") (class "Default")
      (node (ref "Q35") (pin "E") (pinfunction "E_E") (pintype "passive"))
      (node (ref "R41") (pin "1") (pinfunction "1_1") (pintype "passive"))
    )
    (net (code "59") (name "Net-(Q36-PadC)") (class "Default")
      (node (ref "Q36") (pin "C") (pinfunction "C_C") (pintype "passive"))
      (node (ref "R41") (pin "2") (pinfunction "2_2") (pintype "passive"))
      (node (ref "R42") (pin "2") (pinfunction "2_2") (pintype "passive"))
    )
    (net (code "60") (name "Net-(Q36-PadE)") (class "Default")
      (node (ref "Q36") (pin "E") (pinfunction "E_E") (pintype "passive"))
      (node (ref "R43") (pin "1") (pinfunction "1_1") (pintype "passive"))
    )
    (net (code "61") (name "Net-(Q38-C)") (class "Default")
      (node (ref "Q38") (pin "3") (pinfunction "C_3") (pintype "passive"))
      (node (ref "Q40") (pin "C") (pinfunction "C_C") (pintype "passive"))
      (node (ref "Q41") (pin "E") (pinfunction "E_E") (pintype "passive"))
    )
    (net (code "62") (name "Net-(Q38-E)") (class "Default")
      (node (ref "Q38") (pin "2") (pinfunction "E_2") (pintype "passive"))
      (node (ref "R40") (pin "2") (pinfunction "2_2") (pintype "passive"))
    )
    (net (code "63") (name "Net-(Q39-C)") (class "Default")
      (node (ref "Q29") (pin "C") (pinfunction "C_C") (pintype "passive"))
      (node (ref "Q33") (pin "E") (pinfunction "E_E") (pintype "passive"))
      (node (ref "Q39") (pin "3") (pinfunction "C_3") (pintype "passive"))
    )
    (net (code "64") (name "Net-(Q39-E)") (class "Default")
      (node (ref "Q39") (pin "2") (pinfunction "E_2") (pintype "passive"))
      (node (ref "R39") (pin "2") (pinfunction "2_2") (pintype "passive"))
    )
    (net (code "65") (name "Net-(Q40-PadE)") (class "Default")
      (node (ref "Q40") (pin "E") (pinfunction "E_E") (pintype "passive"))
      (node (ref "R36") (pin "1") (pinfunction "1_1") (pintype "passive"))
    )
    (net (code "66") (name "Net-(R3-Pad1)") (class "Default")
      (node (ref "R3") (pin "1") (pinfunction "1_1") (pintype "passive"))
      (node (ref "R4") (pin "2") (pinfunction "2_2") (pintype "passive"))
    )
    (net (code "67") (name "Net-(R19-Pad1)") (class "Default")
      (node (ref "R19") (pin "1") (pinfunction "1_1") (pintype "passive"))
      (node (ref "R20") (pin "2") (pinfunction "2_2") (pintype "passive"))
    )
    (net (code "68") (name "V+") (class "Default")
      (node (ref "C2") (pin "2") (pinfunction "2_2") (pintype "passive"))
      (node (ref "C5") (pin "2") (pinfunction "2_2") (pintype "passive"))
      (node (ref "C7") (pin "+") (pinfunction "+_+") (pintype "passive"))
      (node (ref "C8") (pin "+") (pinfunction "+_+") (pintype "passive"))
      (node (ref "IC1") (pin "7") (pinfunction "V+_7") (pintype "power_in"))
      (node (ref "IC2") (pin "7") (pinfunction "V+_7") (pintype "power_in"))
      (node (ref "LED2") (pin "A") (pinfunction "A_A") (pintype "passive"))
      (node (ref "LED3") (pin "A") (pinfunction "A_A") (pintype "passive"))
      (node (ref "LED5") (pin "A") (pinfunction "A_A") (pintype "passive"))
      (node (ref "LED7") (pin "A") (pinfunction "A_A") (pintype "passive"))
      (node (ref "Q1") (pin "C") (pinfunction "C_C") (pintype "passive"))
      (node (ref "Q13") (pin "C") (pinfunction "C_C") (pintype "passive"))
      (node (ref "Q14") (pin "C") (pinfunction "C_C") (pintype "passive"))
      (node (ref "Q5") (pin "C") (pinfunction "C_C") (pintype "passive"))
      (node (ref "Q8") (pin "C") (pinfunction "C_C") (pintype "passive"))
      (node (ref "Q9") (pin "C") (pinfunction "C_C") (pintype "passive"))
      (node (ref "R1") (pin "2") (pinfunction "2_2") (pintype "passive"))
      (node (ref "R15") (pin "2") (pinfunction "2_2") (pintype "passive"))
      (node (ref "R35") (pin "2") (pinfunction "2_2") (pintype "passive"))
      (node (ref "R36") (pin "2") (pinfunction "2_2") (pintype "passive"))
      (node (ref "R43") (pin "2") (pinfunction "2_2") (pintype "passive"))
      (node (ref "X1") (pin "2") (pinfunction "KL_2") (pintype "passive"))
      (node (ref "X2") (pin "1") (pinfunction "KL_1") (pintype "passive"))
    )
    (net (code "69") (name "V-") (class "Default")
      (node (ref "C10") (pin "-") (pinfunction "-_-") (pintype "passive"))
      (node (ref "C3") (pin "1") (pinfunction "1_1") (pintype "passive"))
      (node (ref "C6") (pin "1") (pinfunction "1_1") (pintype "passive"))
      (node (ref "C9") (pin "-") (pinfunction "-_-") (pintype "passive"))
      (node (ref "IC1") (pin "4") (pinfunction "V-_4") (pintype "power_in"))
      (node (ref "IC2") (pin "4") (pinfunction "V-_4") (pintype "power_in"))
      (node (ref "LED1") (pin "C") (pinfunction "C_C") (pintype "passive"))
      (node (ref "LED4") (pin "C") (pinfunction "C_C") (pintype "passive"))
      (node (ref "LED6") (pin "C") (pinfunction "C_C") (pintype "passive"))
      (node (ref "LED8") (pin "C") (pinfunction "C_C") (pintype "passive"))
      (node (ref "Q10") (pin "C") (pinfunction "C_C") (pintype "passive"))
      (node (ref "Q15") (pin "C") (pinfunction "C_C") (pintype "passive"))
      (node (ref "Q16") (pin "C") (pinfunction "C_C") (pintype "passive"))
      (node (ref "Q2") (pin "C") (pinfunction "C_C") (pintype "passive"))
      (node (ref "Q6") (pin "C") (pinfunction "C_C") (pintype "passive"))
      (node (ref "Q7") (pin "C") (pinfunction "C_C") (pintype "passive"))
      (node (ref "R18") (pin "1") (pinfunction "1_1") (pintype "passive"))
      (node (ref "R2") (pin "1") (pinfunction "1_1") (pintype "passive"))
      (node (ref "R22") (pin "1") (pinfunction "1_1") (pintype "passive"))
      (node (ref "R23") (pin "1") (pinfunction "1_1") (pintype "passive"))
      (node (ref "R44") (pin "1") (pinfunction "1_1") (pintype "passive"))
      (node (ref "X1") (pin "1") (pinfunction "KL_1") (pintype "passive"))
      (node (ref "X2") (pin "2") (pinfunction "KL_2") (pintype "passive"))
    )
    (net (code "70") (name "unconnected-(IC1-TRIM1-Pad1)") (class "Default")
      (node (ref "IC1") (pin "1") (pinfunction "TRIM1_1") (pintype "passive"))
    )
    (net (code "71") (name "unconnected-(IC1-TRIM2-Pad5)") (class "Default")
      (node (ref "IC1") (pin "5") (pinfunction "TRIM2_5") (pintype "passive"))
    )
    (net (code "72") (name "unconnected-(IC2-TRIM1-Pad1)") (class "Default")
      (node (ref "IC2") (pin "1") (pinfunction "TRIM1_1") (pintype "passive"))
    )
    (net (code "73") (name "unconnected-(IC2-TRIM2-Pad5)") (class "Default")
      (node (ref "IC2") (pin "5") (pinfunction "TRIM2_5") (pintype "passive"))
    )
  )
)
